# Pro_Shield_V1.net
KiCad netlist of a schematic drawn in EAGLE
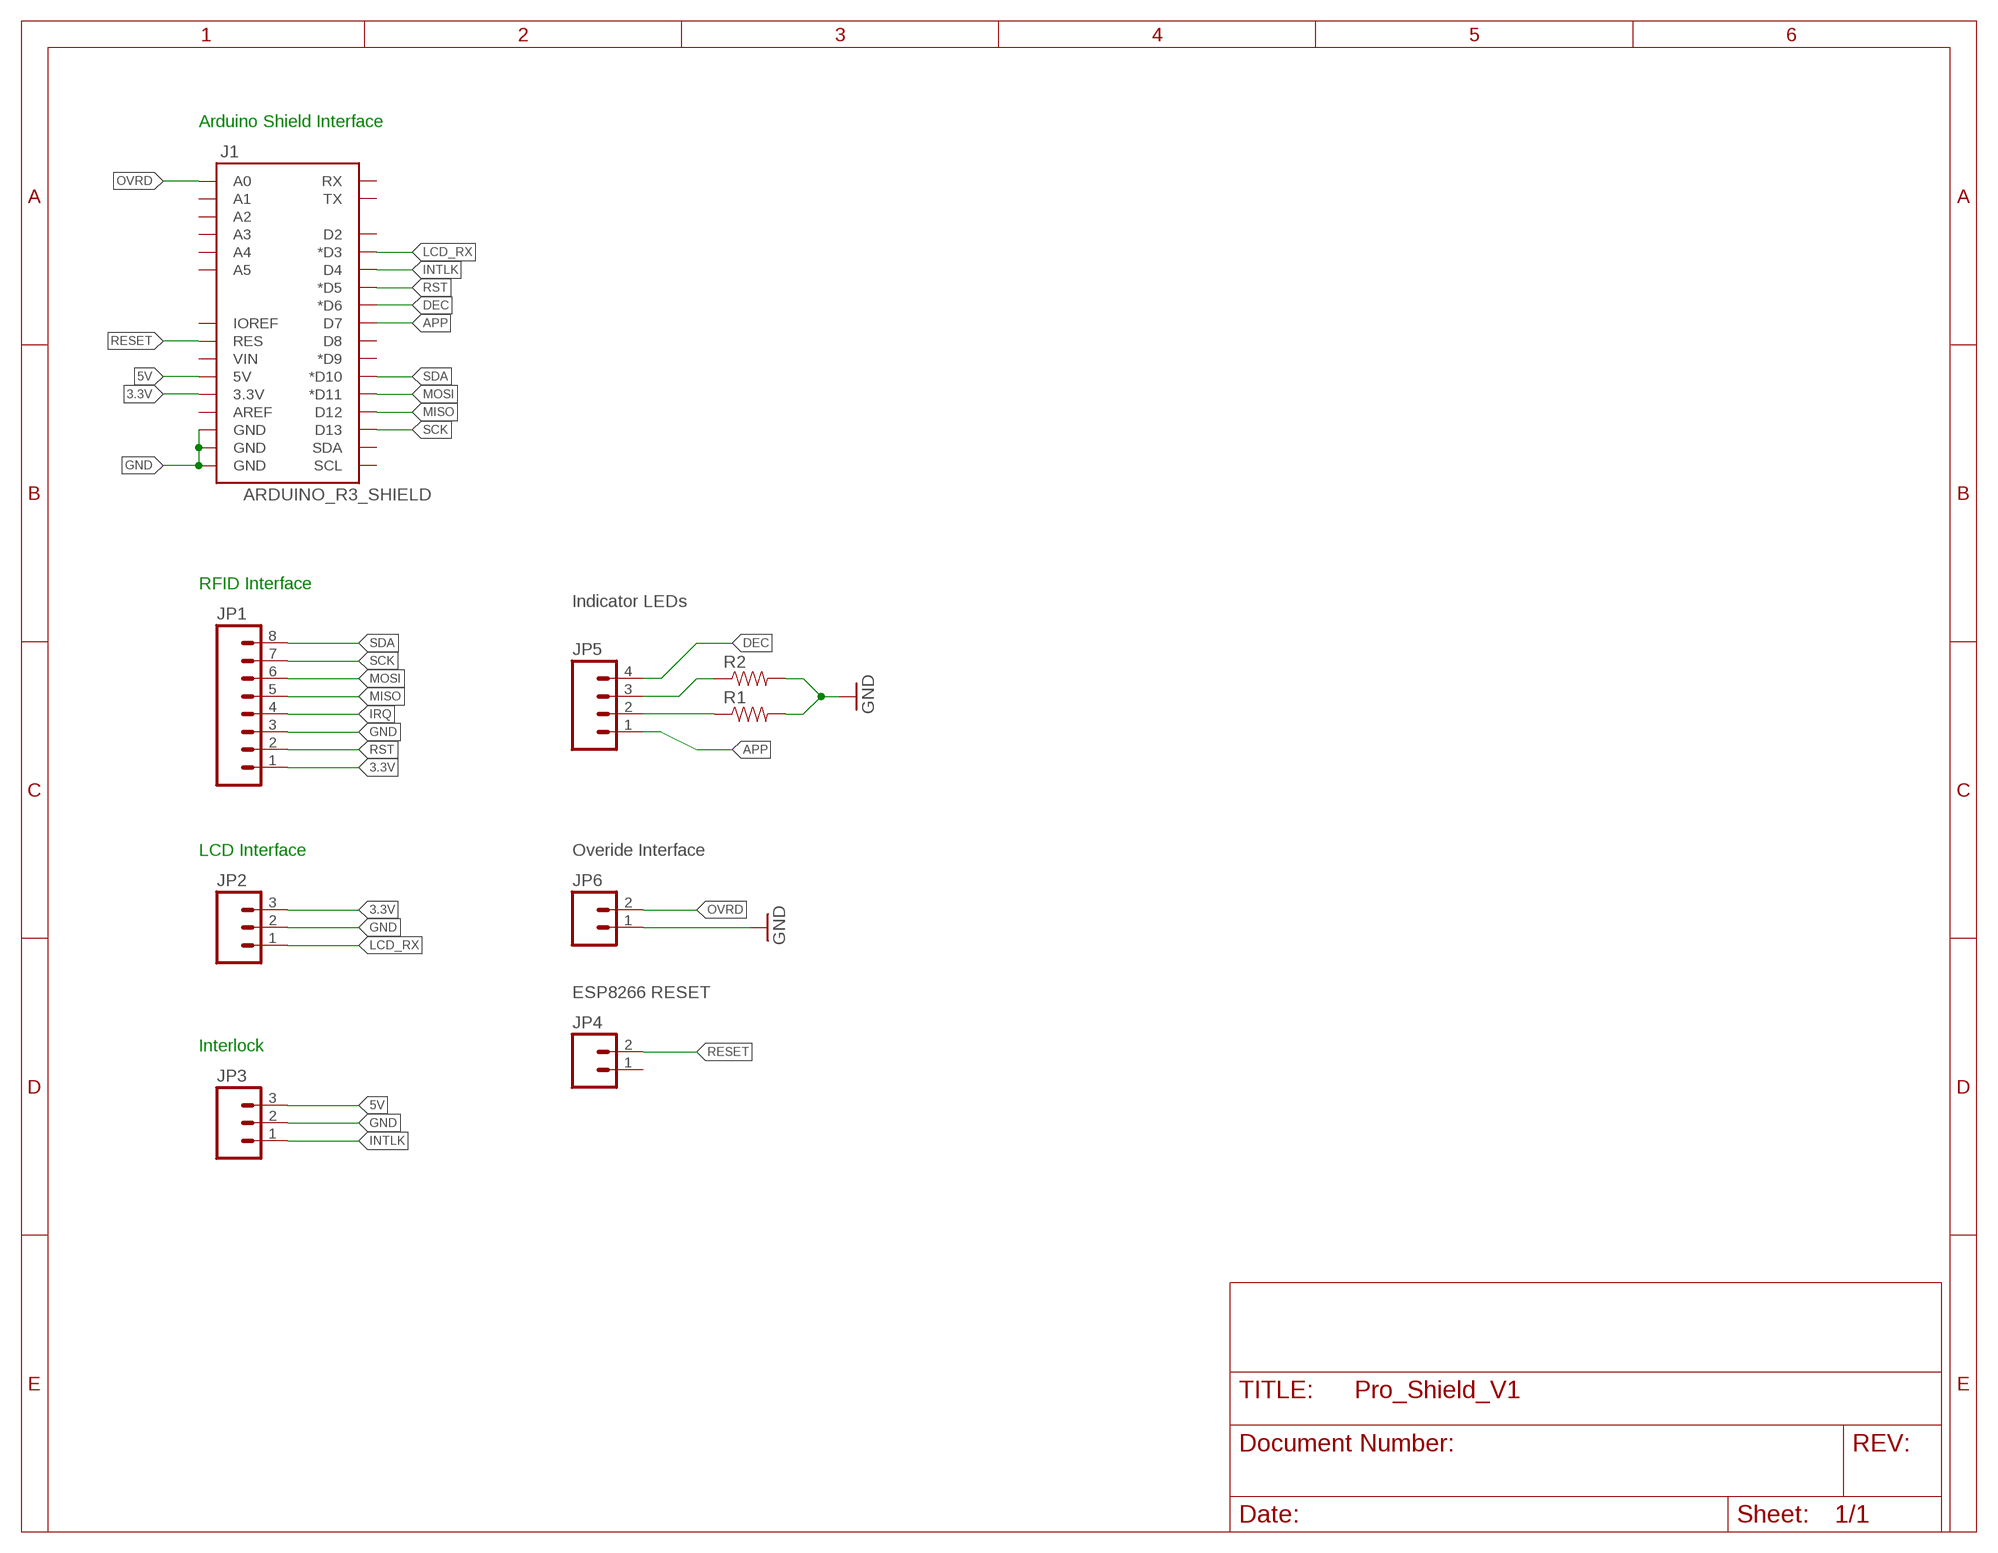
[diagram p0: schematic, sheet 1]

(export (version "E")
  (design (tool "Eeschema 10.0.6"))
  (components
    (comp (ref "J1")
      (value "ARDUINO_R3_SHIELD")
      (footprint "eagle-import:UNO_R3_SHIELD")
      (libsource (lib "eagle-import") (part "ARDUINO_R3_SHIELD"))
    )
    (comp (ref "JP1")
      (value "M08LONGPADS")
      (footprint "eagle-import:1X08_LONGPADS")
      (libsource (lib "eagle-import") (part "M08LONGPADS"))
    )
    (comp (ref "JP2")
      (value "M03LONGPADS")
      (footprint "eagle-import:1X03_LONGPADS")
      (libsource (lib "eagle-import") (part "M03LONGPADS"))
    )
    (comp (ref "JP3")
      (value "M03LONGPADS")
      (footprint "eagle-import:1X03_LONGPADS")
      (libsource (lib "eagle-import") (part "M03LONGPADS"))
    )
    (comp (ref "JP4")
      (value "M02LOCK_LONGPADS")
      (footprint "eagle-import:1X02_LOCK_LONGPADS")
      (libsource (lib "eagle-import") (part "M02LOCK_LONGPADS"))
    )
    (comp (ref "JP5")
      (value "M04LONGPADS")
      (footprint "eagle-import:1X04_LONGPADS")
      (libsource (lib "eagle-import") (part "M04LONGPADS"))
    )
    (comp (ref "JP6")
      (value "M02LOCK_LONGPADS")
      (footprint "eagle-import:1X02_LOCK_LONGPADS")
      (libsource (lib "eagle-import") (part "M02LOCK_LONGPADS"))
    )
    (comp (ref "R1")
      (value "RESISTORPTH-1/4W")
      (footprint "eagle-import:AXIAL-0.4")
      (libsource (lib "eagle-import") (part "RESISTORPTH-1/4W"))
    )
    (comp (ref "R2")
      (value "RESISTORPTH-1/4W")
      (footprint "eagle-import:AXIAL-0.4")
      (libsource (lib "eagle-import") (part "RESISTORPTH-1/4W"))
    )
  )
  (nets
    (net (code "1") (name "3.3V") (class "Default")
      (node (ref "J1") (pin "3.3V") (pinfunction "3.3V_3.3V") (pintype "bidirectional"))
      (node (ref "JP1") (pin "1") (pinfunction "1_1") (pintype "passive"))
      (node (ref "JP2") (pin "3") (pinfunction "3_3") (pintype "passive"))
    )
    (net (code "2") (name "5V") (class "Default")
      (node (ref "J1") (pin "5V") (pinfunction "5V_5V") (pintype "bidirectional"))
      (node (ref "JP3") (pin "3") (pinfunction "3_3") (pintype "passive"))
    )
    (net (code "3") (name "APP") (class "Default")
      (node (ref "J1") (pin "D7") (pinfunction "D7_D7") (pintype "bidirectional"))
      (node (ref "JP5") (pin "1") (pinfunction "1_1") (pintype "passive"))
    )
    (net (code "4") (name "DEC") (class "Default")
      (node (ref "J1") (pin "D6") (pinfunction "*D6_D6") (pintype "bidirectional"))
      (node (ref "JP5") (pin "4") (pinfunction "4_4") (pintype "passive"))
    )
    (net (code "5") (name "GND") (class "Default")
      (node (ref "J1") (pin "GND@0") (pinfunction "GND_GND@0") (pintype "bidirectional"))
      (node (ref "J1") (pin "GND@1") (pinfunction "GND_GND@1") (pintype "bidirectional"))
      (node (ref "J1") (pin "GND@2") (pinfunction "GND_GND@2") (pintype "bidirectional"))
      (node (ref "JP1") (pin "3") (pinfunction "3_3") (pintype "passive"))
      (node (ref "JP2") (pin "2") (pinfunction "2_2") (pintype "passive"))
      (node (ref "JP3") (pin "2") (pinfunction "2_2") (pintype "passive"))
      (node (ref "JP6") (pin "1") (pinfunction "1_1") (pintype "passive"))
      (node (ref "R1") (pin "P$2") (pinfunction "2_P$2") (pintype "passive"))
      (node (ref "R2") (pin "P$2") (pinfunction "2_P$2") (pintype "passive"))
    )
    (net (code "6") (name "INTLK") (class "Default")
      (node (ref "J1") (pin "D4") (pinfunction "D4_D4") (pintype "bidirectional"))
      (node (ref "JP3") (pin "1") (pinfunction "1_1") (pintype "passive"))
    )
    (net (code "7") (name "IRQ") (class "Default")
      (node (ref "JP1") (pin "4") (pinfunction "4_4") (pintype "passive"))
    )
    (net (code "8") (name "LCD_RX") (class "Default")
      (node (ref "J1") (pin "D3") (pinfunction "*D3_D3") (pintype "bidirectional"))
      (node (ref "JP2") (pin "1") (pinfunction "1_1") (pintype "passive"))
    )
    (net (code "9") (name "MISO") (class "Default")
      (node (ref "J1") (pin "D12") (pinfunction "D12_D12") (pintype "bidirectional"))
      (node (ref "JP1") (pin "5") (pinfunction "5_5") (pintype "passive"))
    )
    (net (code "10") (name "MOSI") (class "Default")
      (node (ref "J1") (pin "D11") (pinfunction "*D11_D11") (pintype "bidirectional"))
      (node (ref "JP1") (pin "6") (pinfunction "6_6") (pintype "passive"))
    )
    (net (code "11") (name "Net-(R1-1)") (class "Default")
      (node (ref "JP5") (pin "2") (pinfunction "2_2") (pintype "passive"))
      (node (ref "R1") (pin "P$1") (pinfunction "1_P$1") (pintype "passive"))
    )
    (net (code "12") (name "Net-(R2-1)") (class "Default")
      (node (ref "JP5") (pin "3") (pinfunction "3_3") (pintype "passive"))
      (node (ref "R2") (pin "P$1") (pinfunction "1_P$1") (pintype "passive"))
    )
    (net (code "13") (name "OVRD") (class "Default")
      (node (ref "J1") (pin "A0") (pinfunction "A0_A0") (pintype "bidirectional"))
      (node (ref "JP6") (pin "2") (pinfunction "2_2") (pintype "passive"))
    )
    (net (code "14") (name "RESET") (class "Default")
      (node (ref "J1") (pin "RES") (pinfunction "RES_RES") (pintype "bidirectional"))
      (node (ref "JP4") (pin "2") (pinfunction "2_2") (pintype "passive"))
    )
    (net (code "15") (name "RST") (class "Default")
      (node (ref "J1") (pin "D5") (pinfunction "*D5_D5") (pintype "bidirectional"))
      (node (ref "JP1") (pin "2") (pinfunction "2_2") (pintype "passive"))
    )
    (net (code "16") (name "SCK") (class "Default")
      (node (ref "J1") (pin "D13") (pinfunction "D13_D13") (pintype "bidirectional"))
      (node (ref "JP1") (pin "7") (pinfunction "7_7") (pintype "passive"))
    )
    (net (code "17") (name "SDA") (class "Default")
      (node (ref "J1") (pin "D10") (pinfunction "*D10_D10") (pintype "bidirectional"))
      (node (ref "JP1") (pin "8") (pinfunction "8_8") (pintype "passive"))
    )
    (net (code "18") (name "unconnected-(J1-*D9-PadD9)") (class "Default")
      (node (ref "J1") (pin "D9") (pinfunction "*D9_D9") (pintype "bidirectional"))
    )
    (net (code "19") (name "unconnected-(J1-PadA1)") (class "Default")
      (node (ref "J1") (pin "A1") (pinfunction "A1_A1") (pintype "bidirectional"))
    )
    (net (code "20") (name "unconnected-(J1-PadA2)") (class "Default")
      (node (ref "J1") (pin "A2") (pinfunction "A2_A2") (pintype "bidirectional"))
    )
    (net (code "21") (name "unconnected-(J1-PadA3)") (class "Default")
      (node (ref "J1") (pin "A3") (pinfunction "A3_A3") (pintype "bidirectional"))
    )
    (net (code "22") (name "unconnected-(J1-PadA4)") (class "Default")
      (node (ref "J1") (pin "A4") (pinfunction "A4_A4") (pintype "bidirectional"))
    )
    (net (code "23") (name "unconnected-(J1-PadA5)") (class "Default")
      (node (ref "J1") (pin "A5") (pinfunction "A5_A5") (pintype "bidirectional"))
    )
    (net (code "24") (name "unconnected-(J1-PadAREF)") (class "Default")
      (node (ref "J1") (pin "AREF") (pinfunction "AREF_AREF") (pintype "bidirectional"))
    )
    (net (code "25") (name "unconnected-(J1-PadD2)") (class "Default")
      (node (ref "J1") (pin "D2") (pinfunction "D2_D2") (pintype "bidirectional"))
    )
    (net (code "26") (name "unconnected-(J1-PadD8)") (class "Default")
      (node (ref "J1") (pin "D8") (pinfunction "D8_D8") (pintype "bidirectional"))
    )
    (net (code "27") (name "unconnected-(J1-PadIOREF)") (class "Default")
      (node (ref "J1") (pin "IOREF") (pinfunction "IOREF_IOREF") (pintype "bidirectional"))
    )
    (net (code "28") (name "unconnected-(J1-PadRX)") (class "Default")
      (node (ref "J1") (pin "RX") (pinfunction "RX_RX") (pintype "bidirectional"))
    )
    (net (code "29") (name "unconnected-(J1-PadSCL)") (class "Default")
      (node (ref "J1") (pin "SCL") (pinfunction "SCL_SCL") (pintype "bidirectional"))
    )
    (net (code "30") (name "unconnected-(J1-PadSDA)") (class "Default")
      (node (ref "J1") (pin "SDA") (pinfunction "SDA_SDA") (pintype "bidirectional"))
    )
    (net (code "31") (name "unconnected-(J1-PadTX)") (class "Default")
      (node (ref "J1") (pin "TX") (pinfunction "TX_TX") (pintype "bidirectional"))
    )
    (net (code "32") (name "unconnected-(J1-PadVIN)") (class "Default")
      (node (ref "J1") (pin "VIN") (pinfunction "VIN_VIN") (pintype "bidirectional"))
    )
    (net (code "33") (name "unconnected-(JP4-Pad1)") (class "Default")
      (node (ref "JP4") (pin "1") (pinfunction "1_1") (pintype "passive"))
    )
  )
)
